# W533A.net
KiCad netlist of a schematic drawn in EAGLE
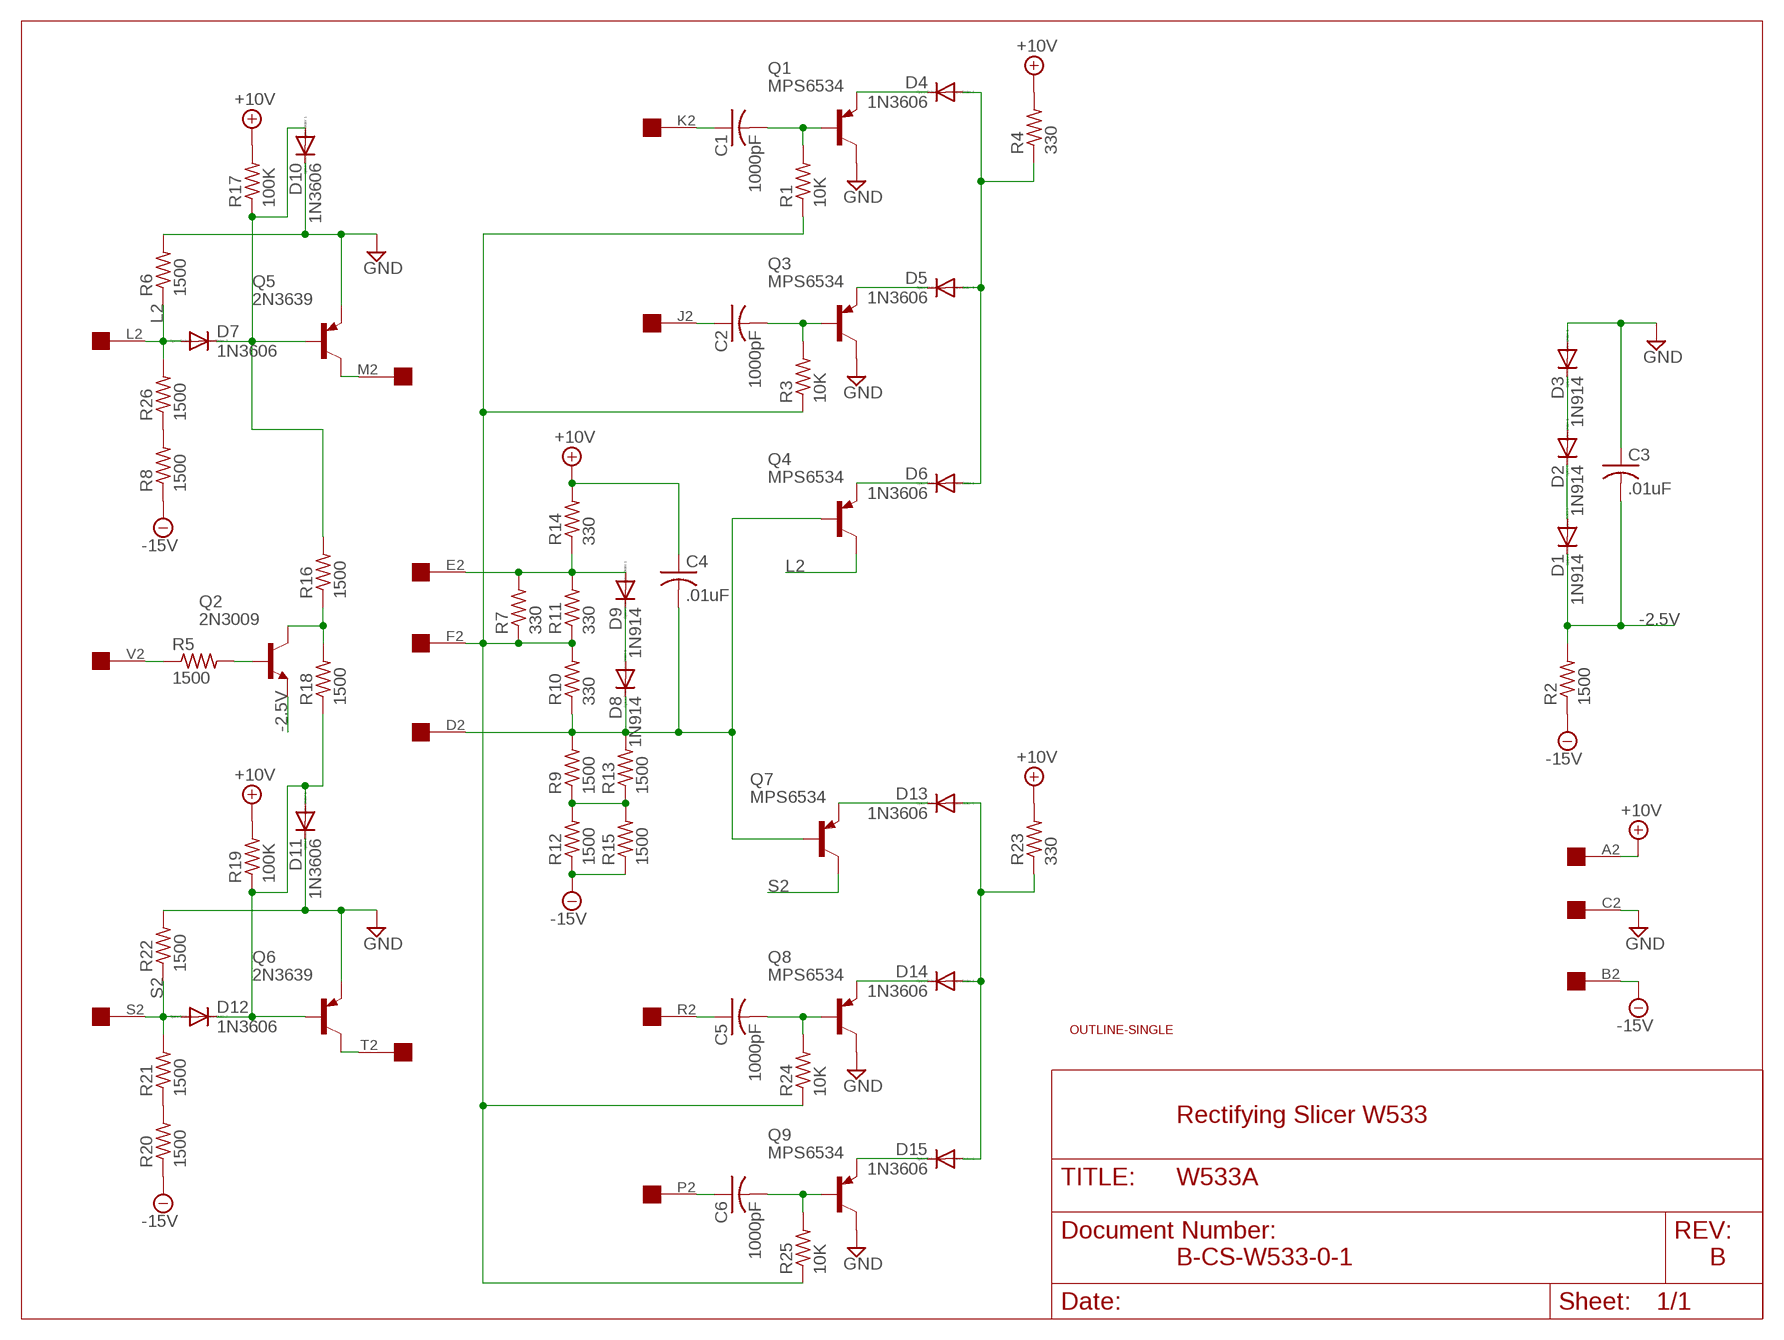
[diagram p0: schematic, sheet 1]

(export (version "E")
  (design (tool "Eeschema 10.0.6"))
  (components
    (comp (ref "C1")
      (value "1000pF")
      (footprint "eagle-import:C075-032X103")
      (libsource (lib "eagle-import") (part "C-US075-032X103"))
    )
    (comp (ref "C2")
      (value "1000pF")
      (footprint "eagle-import:C075-032X103")
      (libsource (lib "eagle-import") (part "C-US075-032X103"))
    )
    (comp (ref "C3")
      (value ".01uF")
      (footprint "eagle-import:C050-025X075")
      (libsource (lib "eagle-import") (part "C-US050-025X075"))
    )
    (comp (ref "C4")
      (value ".01uF")
      (footprint "eagle-import:C050-025X075")
      (libsource (lib "eagle-import") (part "C-US050-025X075"))
    )
    (comp (ref "C5")
      (value "1000pF")
      (footprint "eagle-import:C075-032X103")
      (libsource (lib "eagle-import") (part "C-US075-032X103"))
    )
    (comp (ref "C6")
      (value "1000pF")
      (footprint "eagle-import:C075-032X103")
      (libsource (lib "eagle-import") (part "C-US075-032X103"))
    )
    (comp (ref "D1")
      (value "1N914")
      (footprint "eagle-import:DO35-10")
      (libsource (lib "eagle-import") (part "1N4148DO35-10"))
    )
    (comp (ref "D2")
      (value "1N914")
      (footprint "eagle-import:DO35-10")
      (libsource (lib "eagle-import") (part "1N4148DO35-10"))
    )
    (comp (ref "D3")
      (value "1N914")
      (footprint "eagle-import:DO35-10")
      (libsource (lib "eagle-import") (part "1N4148DO35-10"))
    )
    (comp (ref "D4")
      (value "1N3606")
      (footprint "eagle-import:DO35-10")
      (libsource (lib "eagle-import") (part "1N4148DO35-10"))
    )
    (comp (ref "D5")
      (value "1N3606")
      (footprint "eagle-import:DO35-10")
      (libsource (lib "eagle-import") (part "1N4148DO35-10"))
    )
    (comp (ref "D6")
      (value "1N3606")
      (footprint "eagle-import:DO35-10")
      (libsource (lib "eagle-import") (part "1N4148DO35-10"))
    )
    (comp (ref "D7")
      (value "1N3606")
      (footprint "eagle-import:DO35-10")
      (libsource (lib "eagle-import") (part "1N4148DO35-10"))
    )
    (comp (ref "D8")
      (value "1N914")
      (footprint "eagle-import:DO35-10")
      (libsource (lib "eagle-import") (part "1N4148DO35-10"))
    )
    (comp (ref "D9")
      (value "1N914")
      (footprint "eagle-import:DO35-10")
      (libsource (lib "eagle-import") (part "1N4148DO35-10"))
    )
    (comp (ref "D10")
      (value "1N3606")
      (footprint "eagle-import:DO35-10")
      (libsource (lib "eagle-import") (part "1N4148DO35-10"))
    )
    (comp (ref "D11")
      (value "1N3606")
      (footprint "eagle-import:DO35-10")
      (libsource (lib "eagle-import") (part "1N4148DO35-10"))
    )
    (comp (ref "D12")
      (value "1N3606")
      (footprint "eagle-import:DO35-10")
      (libsource (lib "eagle-import") (part "1N4148DO35-10"))
    )
    (comp (ref "D13")
      (value "1N3606")
      (footprint "eagle-import:DO35-10")
      (libsource (lib "eagle-import") (part "1N4148DO35-10"))
    )
    (comp (ref "D14")
      (value "1N3606")
      (footprint "eagle-import:DO35-10")
      (libsource (lib "eagle-import") (part "1N4148DO35-10"))
    )
    (comp (ref "D15")
      (value "1N3606")
      (footprint "eagle-import:DO35-10")
      (libsource (lib "eagle-import") (part "1N4148DO35-10"))
    )
    (comp (ref "Q1")
      (value "MPS6534")
      (footprint "eagle-import:TO39")
      (libsource (lib "eagle-import") (part "2N2904"))
    )
    (comp (ref "Q2")
      (value "2N3009")
      (footprint "eagle-import:TO5")
      (libsource (lib "eagle-import") (part "2N2102"))
    )
    (comp (ref "Q3")
      (value "MPS6534")
      (footprint "eagle-import:TO39")
      (libsource (lib "eagle-import") (part "2N2904"))
    )
    (comp (ref "Q4")
      (value "MPS6534")
      (footprint "eagle-import:TO39")
      (libsource (lib "eagle-import") (part "2N2904"))
    )
    (comp (ref "Q5")
      (value "2N3639")
      (footprint "eagle-import:TO39")
      (libsource (lib "eagle-import") (part "2N2904"))
    )
    (comp (ref "Q6")
      (value "2N3639")
      (footprint "eagle-import:TO39")
      (libsource (lib "eagle-import") (part "2N2904"))
    )
    (comp (ref "Q7")
      (value "MPS6534")
      (footprint "eagle-import:TO39")
      (libsource (lib "eagle-import") (part "2N2904"))
    )
    (comp (ref "Q8")
      (value "MPS6534")
      (footprint "eagle-import:TO39")
      (libsource (lib "eagle-import") (part "2N2904"))
    )
    (comp (ref "Q9")
      (value "MPS6534")
      (footprint "eagle-import:TO39")
      (libsource (lib "eagle-import") (part "2N2904"))
    )
    (comp (ref "R1")
      (value "10K")
      (footprint "eagle-import:0207_10")
      (libsource (lib "eagle-import") (part "R-US_0207/10"))
    )
    (comp (ref "R2")
      (value "1500")
      (footprint "eagle-import:0207_10")
      (libsource (lib "eagle-import") (part "R-US_0207/10"))
    )
    (comp (ref "R3")
      (value "10K")
      (footprint "eagle-import:0207_10")
      (libsource (lib "eagle-import") (part "R-US_0207/10"))
    )
    (comp (ref "R4")
      (value "330")
      (footprint "eagle-import:0207_10")
      (libsource (lib "eagle-import") (part "R-US_0207/10"))
    )
    (comp (ref "R5")
      (value "1500")
      (footprint "eagle-import:0207_10")
      (libsource (lib "eagle-import") (part "R-US_0207/10"))
    )
    (comp (ref "R6")
      (value "1500")
      (footprint "eagle-import:0207_10")
      (libsource (lib "eagle-import") (part "R-US_0207/10"))
    )
    (comp (ref "R7")
      (value "330")
      (footprint "eagle-import:0207_10")
      (libsource (lib "eagle-import") (part "R-US_0207/10"))
    )
    (comp (ref "R8")
      (value "1500")
      (footprint "eagle-import:0207_10")
      (libsource (lib "eagle-import") (part "R-US_0207/10"))
    )
    (comp (ref "R9")
      (value "1500")
      (footprint "eagle-import:0207_10")
      (libsource (lib "eagle-import") (part "R-US_0207/10"))
    )
    (comp (ref "R10")
      (value "330")
      (footprint "eagle-import:0207_10")
      (libsource (lib "eagle-import") (part "R-US_0207/10"))
    )
    (comp (ref "R11")
      (value "330")
      (footprint "eagle-import:0207_10")
      (libsource (lib "eagle-import") (part "R-US_0207/10"))
    )
    (comp (ref "R12")
      (value "1500")
      (footprint "eagle-import:0207_10")
      (libsource (lib "eagle-import") (part "R-US_0207/10"))
    )
    (comp (ref "R13")
      (value "1500")
      (footprint "eagle-import:0207_10")
      (libsource (lib "eagle-import") (part "R-US_0207/10"))
    )
    (comp (ref "R14")
      (value "330")
      (footprint "eagle-import:0207_10")
      (libsource (lib "eagle-import") (part "R-US_0207/10"))
    )
    (comp (ref "R15")
      (value "1500")
      (footprint "eagle-import:0207_10")
      (libsource (lib "eagle-import") (part "R-US_0207/10"))
    )
    (comp (ref "R16")
      (value "1500")
      (footprint "eagle-import:0207_10")
      (libsource (lib "eagle-import") (part "R-US_0207/10"))
    )
    (comp (ref "R17")
      (value "100K")
      (footprint "eagle-import:0207_10")
      (libsource (lib "eagle-import") (part "R-US_0207/10"))
    )
    (comp (ref "R18")
      (value "1500")
      (footprint "eagle-import:0207_10")
      (libsource (lib "eagle-import") (part "R-US_0207/10"))
    )
    (comp (ref "R19")
      (value "100K")
      (footprint "eagle-import:0207_10")
      (libsource (lib "eagle-import") (part "R-US_0207/10"))
    )
    (comp (ref "R20")
      (value "1500")
      (footprint "eagle-import:0207_10")
      (libsource (lib "eagle-import") (part "R-US_0207/10"))
    )
    (comp (ref "R21")
      (value "1500")
      (footprint "eagle-import:0207_10")
      (libsource (lib "eagle-import") (part "R-US_0207/10"))
    )
    (comp (ref "R22")
      (value "1500")
      (footprint "eagle-import:0207_10")
      (libsource (lib "eagle-import") (part "R-US_0207/10"))
    )
    (comp (ref "R23")
      (value "330")
      (footprint "eagle-import:0207_10")
      (libsource (lib "eagle-import") (part "R-US_0207/10"))
    )
    (comp (ref "R24")
      (value "10K")
      (footprint "eagle-import:0207_10")
      (libsource (lib "eagle-import") (part "R-US_0207/10"))
    )
    (comp (ref "R25")
      (value "10K")
      (footprint "eagle-import:0207_10")
      (libsource (lib "eagle-import") (part "R-US_0207/10"))
    )
    (comp (ref "R26")
      (value "1500")
      (footprint "eagle-import:0207_10")
      (libsource (lib "eagle-import") (part "R-US_0207/10"))
    )
    (comp (ref "U$1")
      (value "OUTLINE-SINGLE")
      (footprint "eagle-import:SINGLE")
      (libsource (lib "eagle-import") (part "OUTLINE-SINGLE"))
    )
    (comp (ref "U$2")
      (value "EDGE-1")
      (footprint "eagle-import:EDGE-CON1")
      (libsource (lib "eagle-import") (part "EDGE-1"))
    )
  )
  (nets
    (net (code "1") (name "+10V") (class "Default")
      (node (ref "C4") (pin "1") (pinfunction "1_1") (pintype "passive"))
      (node (ref "R14") (pin "2") (pinfunction "2_2") (pintype "passive"))
      (node (ref "R17") (pin "2") (pinfunction "2_2") (pintype "passive"))
      (node (ref "R19") (pin "2") (pinfunction "2_2") (pintype "passive"))
      (node (ref "R23") (pin "2") (pinfunction "2_2") (pintype "passive"))
      (node (ref "R4") (pin "2") (pinfunction "2_2") (pintype "passive"))
      (node (ref "U$2") (pin "A2") (pinfunction "1_A2") (pintype "bidirectional"))
    )
    (net (code "2") (name "-15V") (class "Default")
      (node (ref "R12") (pin "1") (pinfunction "1_1") (pintype "passive"))
      (node (ref "R15") (pin "1") (pinfunction "1_1") (pintype "passive"))
      (node (ref "R2") (pin "1") (pinfunction "1_1") (pintype "passive"))
      (node (ref "R20") (pin "1") (pinfunction "1_1") (pintype "passive"))
      (node (ref "R8") (pin "1") (pinfunction "1_1") (pintype "passive"))
      (node (ref "U$2") (pin "B2") (pinfunction "1_B2") (pintype "bidirectional"))
    )
    (net (code "3") (name "/-2.5V") (class "Default")
      (node (ref "C3") (pin "2") (pinfunction "2_2") (pintype "passive"))
      (node (ref "D1") (pin "C") (pinfunction "C_C") (pintype "passive"))
      (node (ref "Q2") (pin "1") (pinfunction "E_1") (pintype "passive"))
      (node (ref "R2") (pin "2") (pinfunction "2_2") (pintype "passive"))
    )
    (net (code "4") (name "/L2") (class "Default")
      (node (ref "D7") (pin "A") (pinfunction "A_A") (pintype "passive"))
      (node (ref "Q4") (pin "3") (pinfunction "C_3") (pintype "passive"))
      (node (ref "R26") (pin "2") (pinfunction "2_2") (pintype "passive"))
      (node (ref "R6") (pin "1") (pinfunction "1_1") (pintype "passive"))
      (node (ref "U$2") (pin "L2") (pinfunction "1_L2") (pintype "bidirectional"))
    )
    (net (code "5") (name "/S2") (class "Default")
      (node (ref "D12") (pin "A") (pinfunction "A_A") (pintype "passive"))
      (node (ref "Q7") (pin "3") (pinfunction "C_3") (pintype "passive"))
      (node (ref "R21") (pin "2") (pinfunction "2_2") (pintype "passive"))
      (node (ref "R22") (pin "1") (pinfunction "1_1") (pintype "passive"))
      (node (ref "U$2") (pin "S2") (pinfunction "1_S2") (pintype "bidirectional"))
    )
    (net (code "6") (name "GND") (class "Default")
      (node (ref "C3") (pin "1") (pinfunction "1_1") (pintype "passive"))
      (node (ref "D10") (pin "C") (pinfunction "C_C") (pintype "passive"))
      (node (ref "D11") (pin "C") (pinfunction "C_C") (pintype "passive"))
      (node (ref "D3") (pin "A") (pinfunction "A_A") (pintype "passive"))
      (node (ref "Q1") (pin "3") (pinfunction "C_3") (pintype "passive"))
      (node (ref "Q3") (pin "3") (pinfunction "C_3") (pintype "passive"))
      (node (ref "Q5") (pin "1") (pinfunction "E_1") (pintype "passive"))
      (node (ref "Q6") (pin "1") (pinfunction "E_1") (pintype "passive"))
      (node (ref "Q8") (pin "3") (pinfunction "C_3") (pintype "passive"))
      (node (ref "Q9") (pin "3") (pinfunction "C_3") (pintype "passive"))
      (node (ref "R22") (pin "2") (pinfunction "2_2") (pintype "passive"))
      (node (ref "R6") (pin "2") (pinfunction "2_2") (pintype "passive"))
      (node (ref "U$2") (pin "C2") (pinfunction "1_C2") (pintype "bidirectional"))
    )
    (net (code "7") (name "Net-(D1-PadA)") (class "Default")
      (node (ref "D1") (pin "A") (pinfunction "A_A") (pintype "passive"))
      (node (ref "D2") (pin "C") (pinfunction "C_C") (pintype "passive"))
    )
    (net (code "8") (name "Net-(D2-PadA)") (class "Default")
      (node (ref "D2") (pin "A") (pinfunction "A_A") (pintype "passive"))
      (node (ref "D3") (pin "C") (pinfunction "C_C") (pintype "passive"))
    )
    (net (code "9") (name "Net-(D4-PadA)") (class "Default")
      (node (ref "D4") (pin "A") (pinfunction "A_A") (pintype "passive"))
      (node (ref "D5") (pin "A") (pinfunction "A_A") (pintype "passive"))
      (node (ref "D6") (pin "A") (pinfunction "A_A") (pintype "passive"))
      (node (ref "R4") (pin "1") (pinfunction "1_1") (pintype "passive"))
    )
    (net (code "10") (name "Net-(D8-PadA)") (class "Default")
      (node (ref "D8") (pin "A") (pinfunction "A_A") (pintype "passive"))
      (node (ref "D9") (pin "C") (pinfunction "C_C") (pintype "passive"))
    )
    (net (code "11") (name "Net-(D13-PadA)") (class "Default")
      (node (ref "D13") (pin "A") (pinfunction "A_A") (pintype "passive"))
      (node (ref "D14") (pin "A") (pinfunction "A_A") (pintype "passive"))
      (node (ref "D15") (pin "A") (pinfunction "A_A") (pintype "passive"))
      (node (ref "R23") (pin "1") (pinfunction "1_1") (pintype "passive"))
    )
    (net (code "12") (name "Net-(Q1-B)") (class "Default")
      (node (ref "C1") (pin "2") (pinfunction "2_2") (pintype "passive"))
      (node (ref "Q1") (pin "2") (pinfunction "B_2") (pintype "passive"))
      (node (ref "R1") (pin "2") (pinfunction "2_2") (pintype "passive"))
    )
    (net (code "13") (name "Net-(Q1-E)") (class "Default")
      (node (ref "D4") (pin "C") (pinfunction "C_C") (pintype "passive"))
      (node (ref "Q1") (pin "1") (pinfunction "E_1") (pintype "passive"))
    )
    (net (code "14") (name "Net-(Q2-B)") (class "Default")
      (node (ref "Q2") (pin "2") (pinfunction "B_2") (pintype "passive"))
      (node (ref "R5") (pin "2") (pinfunction "2_2") (pintype "passive"))
    )
    (net (code "15") (name "Net-(Q2-C)") (class "Default")
      (node (ref "Q2") (pin "3") (pinfunction "C_3") (pintype "passive"))
      (node (ref "R16") (pin "1") (pinfunction "1_1") (pintype "passive"))
      (node (ref "R18") (pin "2") (pinfunction "2_2") (pintype "passive"))
    )
    (net (code "16") (name "Net-(Q3-B)") (class "Default")
      (node (ref "C2") (pin "2") (pinfunction "2_2") (pintype "passive"))
      (node (ref "Q3") (pin "2") (pinfunction "B_2") (pintype "passive"))
      (node (ref "R3") (pin "2") (pinfunction "2_2") (pintype "passive"))
    )
    (net (code "17") (name "Net-(Q3-E)") (class "Default")
      (node (ref "D5") (pin "C") (pinfunction "C_C") (pintype "passive"))
      (node (ref "Q3") (pin "1") (pinfunction "E_1") (pintype "passive"))
    )
    (net (code "18") (name "Net-(Q4-B)") (class "Default")
      (node (ref "C4") (pin "2") (pinfunction "2_2") (pintype "passive"))
      (node (ref "D8") (pin "C") (pinfunction "C_C") (pintype "passive"))
      (node (ref "Q4") (pin "2") (pinfunction "B_2") (pintype "passive"))
      (node (ref "Q7") (pin "2") (pinfunction "B_2") (pintype "passive"))
      (node (ref "R10") (pin "1") (pinfunction "1_1") (pintype "passive"))
      (node (ref "R13") (pin "2") (pinfunction "2_2") (pintype "passive"))
      (node (ref "R9") (pin "2") (pinfunction "2_2") (pintype "passive"))
      (node (ref "U$2") (pin "D2") (pinfunction "1_D2") (pintype "bidirectional"))
    )
    (net (code "19") (name "Net-(Q4-E)") (class "Default")
      (node (ref "D6") (pin "C") (pinfunction "C_C") (pintype "passive"))
      (node (ref "Q4") (pin "1") (pinfunction "E_1") (pintype "passive"))
    )
    (net (code "20") (name "Net-(Q5-B)") (class "Default")
      (node (ref "D10") (pin "A") (pinfunction "A_A") (pintype "passive"))
      (node (ref "D7") (pin "C") (pinfunction "C_C") (pintype "passive"))
      (node (ref "Q5") (pin "2") (pinfunction "B_2") (pintype "passive"))
      (node (ref "R16") (pin "2") (pinfunction "2_2") (pintype "passive"))
      (node (ref "R17") (pin "1") (pinfunction "1_1") (pintype "passive"))
    )
    (net (code "21") (name "Net-(Q5-C)") (class "Default")
      (node (ref "Q5") (pin "3") (pinfunction "C_3") (pintype "passive"))
      (node (ref "U$2") (pin "M2") (pinfunction "1_M2") (pintype "bidirectional"))
    )
    (net (code "22") (name "Net-(Q6-B)") (class "Default")
      (node (ref "D11") (pin "A") (pinfunction "A_A") (pintype "passive"))
      (node (ref "D12") (pin "C") (pinfunction "C_C") (pintype "passive"))
      (node (ref "Q6") (pin "2") (pinfunction "B_2") (pintype "passive"))
      (node (ref "R18") (pin "1") (pinfunction "1_1") (pintype "passive"))
      (node (ref "R19") (pin "1") (pinfunction "1_1") (pintype "passive"))
    )
    (net (code "23") (name "Net-(Q6-C)") (class "Default")
      (node (ref "Q6") (pin "3") (pinfunction "C_3") (pintype "passive"))
      (node (ref "U$2") (pin "T2") (pinfunction "1_T2") (pintype "bidirectional"))
    )
    (net (code "24") (name "Net-(Q7-E)") (class "Default")
      (node (ref "D13") (pin "C") (pinfunction "C_C") (pintype "passive"))
      (node (ref "Q7") (pin "1") (pinfunction "E_1") (pintype "passive"))
    )
    (net (code "25") (name "Net-(Q8-B)") (class "Default")
      (node (ref "C5") (pin "2") (pinfunction "2_2") (pintype "passive"))
      (node (ref "Q8") (pin "2") (pinfunction "B_2") (pintype "passive"))
      (node (ref "R24") (pin "2") (pinfunction "2_2") (pintype "passive"))
    )
    (net (code "26") (name "Net-(Q8-E)") (class "Default")
      (node (ref "D14") (pin "C") (pinfunction "C_C") (pintype "passive"))
      (node (ref "Q8") (pin "1") (pinfunction "E_1") (pintype "passive"))
    )
    (net (code "27") (name "Net-(Q9-B)") (class "Default")
      (node (ref "C6") (pin "2") (pinfunction "2_2") (pintype "passive"))
      (node (ref "Q9") (pin "2") (pinfunction "B_2") (pintype "passive"))
      (node (ref "R25") (pin "2") (pinfunction "2_2") (pintype "passive"))
    )
    (net (code "28") (name "Net-(Q9-E)") (class "Default")
      (node (ref "D15") (pin "C") (pinfunction "C_C") (pintype "passive"))
      (node (ref "Q9") (pin "1") (pinfunction "E_1") (pintype "passive"))
    )
    (net (code "29") (name "Net-(R12-Pad2)") (class "Default")
      (node (ref "R12") (pin "2") (pinfunction "2_2") (pintype "passive"))
      (node (ref "R13") (pin "1") (pinfunction "1_1") (pintype "passive"))
      (node (ref "R15") (pin "2") (pinfunction "2_2") (pintype "passive"))
      (node (ref "R9") (pin "1") (pinfunction "1_1") (pintype "passive"))
    )
    (net (code "30") (name "Net-(R20-Pad2)") (class "Default")
      (node (ref "R20") (pin "2") (pinfunction "2_2") (pintype "passive"))
      (node (ref "R21") (pin "1") (pinfunction "1_1") (pintype "passive"))
    )
    (net (code "31") (name "Net-(R26-Pad1)") (class "Default")
      (node (ref "R26") (pin "1") (pinfunction "1_1") (pintype "passive"))
      (node (ref "R8") (pin "2") (pinfunction "2_2") (pintype "passive"))
    )
    (net (code "32") (name "Net-(U$2E-1)") (class "Default")
      (node (ref "D9") (pin "A") (pinfunction "A_A") (pintype "passive"))
      (node (ref "R11") (pin "2") (pinfunction "2_2") (pintype "passive"))
      (node (ref "R14") (pin "1") (pinfunction "1_1") (pintype "passive"))
      (node (ref "R7") (pin "2") (pinfunction "2_2") (pintype "passive"))
      (node (ref "U$2") (pin "E2") (pinfunction "1_E2") (pintype "bidirectional"))
    )
    (net (code "33") (name "Net-(U$2F-1)") (class "Default")
      (node (ref "R1") (pin "1") (pinfunction "1_1") (pintype "passive"))
      (node (ref "R10") (pin "2") (pinfunction "2_2") (pintype "passive"))
      (node (ref "R11") (pin "1") (pinfunction "1_1") (pintype "passive"))
      (node (ref "R24") (pin "1") (pinfunction "1_1") (pintype "passive"))
      (node (ref "R25") (pin "1") (pinfunction "1_1") (pintype "passive"))
      (node (ref "R3") (pin "1") (pinfunction "1_1") (pintype "passive"))
      (node (ref "R7") (pin "1") (pinfunction "1_1") (pintype "passive"))
      (node (ref "U$2") (pin "F2") (pinfunction "1_F2") (pintype "bidirectional"))
    )
    (net (code "34") (name "Net-(U$2H-1)") (class "Default")
      (node (ref "C2") (pin "1") (pinfunction "1_1") (pintype "passive"))
      (node (ref "U$2") (pin "J2") (pinfunction "1_J2") (pintype "bidirectional"))
    )
    (net (code "35") (name "Net-(U$2I-1)") (class "Default")
      (node (ref "C1") (pin "1") (pinfunction "1_1") (pintype "passive"))
      (node (ref "U$2") (pin "K2") (pinfunction "1_K2") (pintype "bidirectional"))
    )
    (net (code "36") (name "Net-(U$2M-1)") (class "Default")
      (node (ref "C6") (pin "1") (pinfunction "1_1") (pintype "passive"))
      (node (ref "U$2") (pin "P2") (pinfunction "1_P2") (pintype "bidirectional"))
    )
    (net (code "37") (name "Net-(U$2N-1)") (class "Default")
      (node (ref "C5") (pin "1") (pinfunction "1_1") (pintype "passive"))
      (node (ref "U$2") (pin "R2") (pinfunction "1_R2") (pintype "bidirectional"))
    )
    (net (code "38") (name "Net-(U$2R-1)") (class "Default")
      (node (ref "R5") (pin "1") (pinfunction "1_1") (pintype "passive"))
      (node (ref "U$2") (pin "V2") (pinfunction "1_V2") (pintype "bidirectional"))
    )
  )
)
